# linus_v1_R2.net
KiCad netlist of a schematic drawn in EAGLE
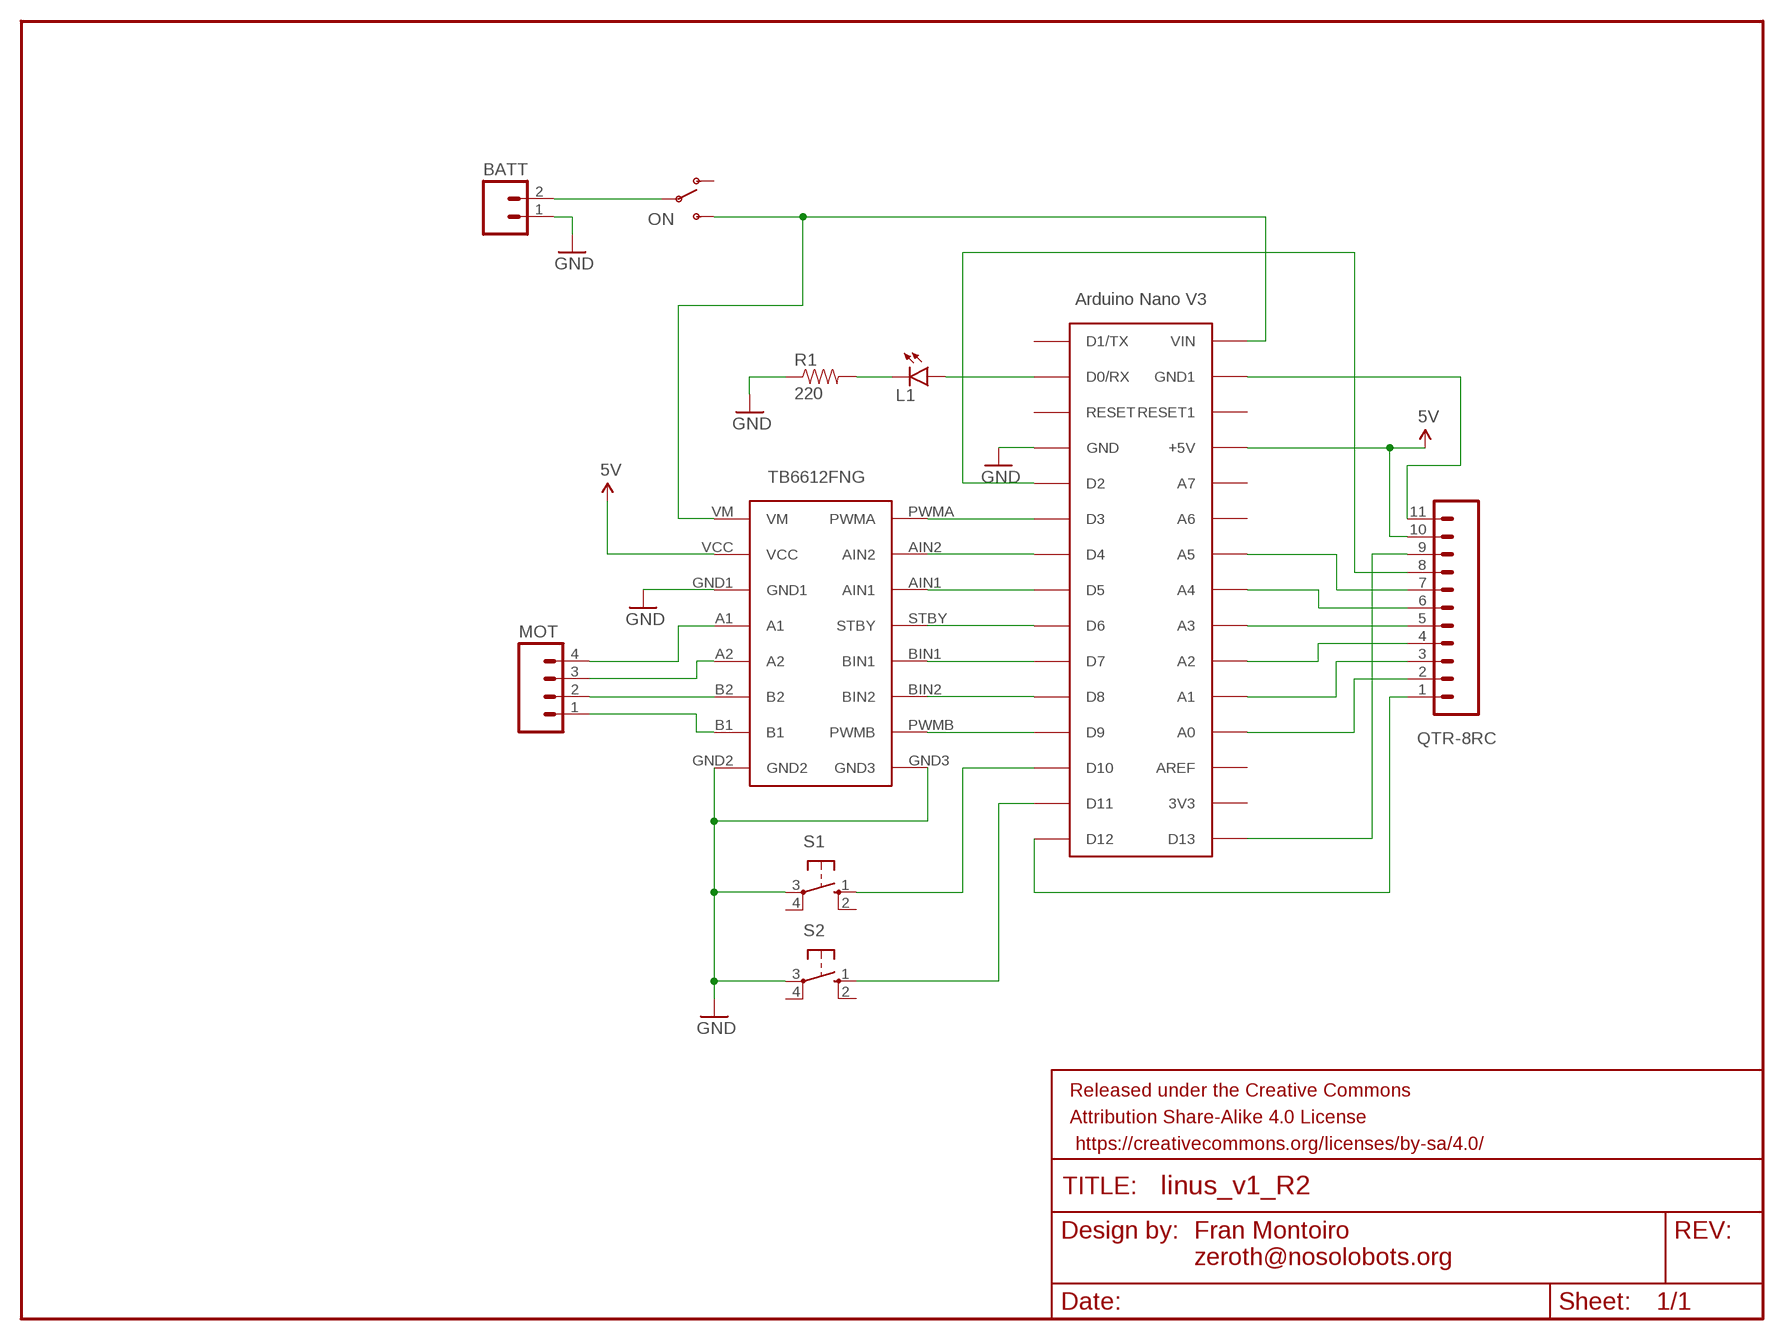
[diagram p0: schematic, sheet 1]

(export (version "E")
  (design (tool "Eeschema 10.0.6"))
  (components
    (comp (ref "BATT")
      (value "M02PTH")
      (footprint "eagle-import:1X02")
      (libsource (lib "eagle-import") (part "M02PTH"))
    )
    (comp (ref "FRAME1")
      (value "FRAME-LETTERNO_PACKAGE")
      (footprint "eagle-import:DUMMY")
      (fields (field (name "DESIGNER") "Nobody"))
      (libsource (lib "eagle-import") (part "FRAME-LETTERNO_PACKAGE"))
    )
    (comp (ref "L1")
      (value "LED5MM")
      (footprint "eagle-import:LED5MM")
      (libsource (lib "eagle-import") (part "LED5MM"))
    )
    (comp (ref "MOT")
      (value "M04PTH")
      (footprint "eagle-import:1X04")
      (libsource (lib "eagle-import") (part "M04PTH"))
    )
    (comp (ref "ON")
      (value "SWITCH-SPDTPTH")
      (footprint "eagle-import:SWITCH-SPDT")
      (libsource (lib "eagle-import") (part "SWITCH-SPDTPTH"))
    )
    (comp (ref "QTR-8RC")
      (value "M11PTH")
      (footprint "eagle-import:1X11")
      (libsource (lib "eagle-import") (part "M11PTH"))
    )
    (comp (ref "R1")
      (value "220")
      (footprint "eagle-import:AXIAL-0.4")
      (libsource (lib "eagle-import") (part "RESISTORPTH-1/4W"))
    )
    (comp (ref "S1")
      (value "10-XX")
      (footprint "eagle-import:B3F-10XX")
      (fields (field (name "MPN") "B3F-1000"))
      (libsource (lib "eagle-import") (part "10-XX"))
    )
    (comp (ref "S2")
      (value "10-XX")
      (footprint "eagle-import:B3F-10XX")
      (fields (field (name "MPN") "B3F-1000"))
      (libsource (lib "eagle-import") (part "10-XX"))
    )
    (comp (ref "TB1")
      (value "TB6612FNG")
      (footprint "eagle-import:TB6612FNG")
      (libsource (lib "eagle-import") (part "TB6612FNG"))
    )
    (comp (ref "U$1")
      (value "ARDUINONANO")
      (footprint "eagle-import:PDIP-32")
      (libsource (lib "eagle-import") (part "ARDUINONANO"))
    )
  )
  (nets
    (net (code "1") (name "5V") (class "Default")
      (node (ref "QTR-8RC") (pin "10") (pinfunction "10_10") (pintype "passive"))
      (node (ref "TB1") (pin "VCC") (pinfunction "VCC_VCC") (pintype "bidirectional"))
      (node (ref "U$1") (pin "+5V") (pinfunction "+5V_+5V") (pintype "bidirectional"))
    )
    (net (code "2") (name "GND") (class "Default")
      (node (ref "BATT") (pin "1") (pinfunction "1_1") (pintype "passive"))
      (node (ref "R1") (pin "P$1") (pinfunction "1_P$1") (pintype "passive"))
      (node (ref "S1") (pin "3") (pinfunction "P_3") (pintype "passive"))
      (node (ref "S2") (pin "3") (pinfunction "P_3") (pintype "passive"))
      (node (ref "TB1") (pin "GND1") (pinfunction "GND1_GND1") (pintype "bidirectional"))
      (node (ref "TB1") (pin "GND2") (pinfunction "GND2_GND2") (pintype "bidirectional"))
      (node (ref "TB1") (pin "GND3") (pinfunction "GND3_GND3") (pintype "bidirectional"))
      (node (ref "U$1") (pin "GND") (pinfunction "GND_GND") (pintype "bidirectional"))
    )
    (net (code "3") (name "Net-(L1-C)") (class "Default")
      (node (ref "L1") (pin "K") (pinfunction "C_K") (pintype "passive"))
      (node (ref "R1") (pin "P$2") (pinfunction "2_P$2") (pintype "passive"))
    )
    (net (code "4") (name "Net-(L1-PadA)") (class "Default")
      (node (ref "L1") (pin "A") (pinfunction "A_A") (pintype "passive"))
      (node (ref "U$1") (pin "D0/RX") (pinfunction "D0/RX_D0/RX") (pintype "bidirectional"))
    )
    (net (code "5") (name "Net-(MOT-Pad1)") (class "Default")
      (node (ref "MOT") (pin "1") (pinfunction "1_1") (pintype "passive"))
      (node (ref "TB1") (pin "B1") (pinfunction "B1_B1") (pintype "bidirectional"))
    )
    (net (code "6") (name "Net-(MOT-Pad2)") (class "Default")
      (node (ref "MOT") (pin "2") (pinfunction "2_2") (pintype "passive"))
      (node (ref "TB1") (pin "B2") (pinfunction "B2_B2") (pintype "bidirectional"))
    )
    (net (code "7") (name "Net-(MOT-Pad3)") (class "Default")
      (node (ref "MOT") (pin "3") (pinfunction "3_3") (pintype "passive"))
      (node (ref "TB1") (pin "A2") (pinfunction "A2_A2") (pintype "bidirectional"))
    )
    (net (code "8") (name "Net-(MOT-Pad4)") (class "Default")
      (node (ref "MOT") (pin "4") (pinfunction "4_4") (pintype "passive"))
      (node (ref "TB1") (pin "A1") (pinfunction "A1_A1") (pintype "bidirectional"))
    )
    (net (code "9") (name "Net-(ON-P)") (class "Default")
      (node (ref "BATT") (pin "2") (pinfunction "2_2") (pintype "passive"))
      (node (ref "ON") (pin "2") (pinfunction "P_2") (pintype "passive"))
    )
    (net (code "10") (name "Net-(ON-S)") (class "Default")
      (node (ref "ON") (pin "3") (pinfunction "S_3") (pintype "passive"))
      (node (ref "TB1") (pin "VM") (pinfunction "VM_VM") (pintype "bidirectional"))
      (node (ref "U$1") (pin "VIN") (pinfunction "VIN_VIN") (pintype "bidirectional"))
    )
    (net (code "11") (name "Net-(QTR-8RC-Pad1)") (class "Default")
      (node (ref "QTR-8RC") (pin "1") (pinfunction "1_1") (pintype "passive"))
      (node (ref "U$1") (pin "D12") (pinfunction "D12_D12") (pintype "bidirectional"))
    )
    (net (code "12") (name "Net-(QTR-8RC-Pad8)") (class "Default")
      (node (ref "QTR-8RC") (pin "8") (pinfunction "8_8") (pintype "passive"))
      (node (ref "U$1") (pin "D2") (pinfunction "D2_D2") (pintype "bidirectional"))
    )
    (net (code "13") (name "Net-(QTR-8RC-Pad9)") (class "Default")
      (node (ref "QTR-8RC") (pin "9") (pinfunction "9_9") (pintype "passive"))
      (node (ref "U$1") (pin "D13") (pinfunction "D13_D13") (pintype "bidirectional"))
    )
    (net (code "14") (name "Net-(QTR-8RC-Pad11)") (class "Default")
      (node (ref "QTR-8RC") (pin "11") (pinfunction "11_11") (pintype "passive"))
      (node (ref "U$1") (pin "GND1") (pinfunction "GND1_GND1") (pintype "bidirectional"))
    )
    (net (code "15") (name "Net-(S1-S)") (class "Default")
      (node (ref "S1") (pin "1") (pinfunction "S_1") (pintype "passive"))
      (node (ref "U$1") (pin "D10") (pinfunction "D10_D10") (pintype "bidirectional"))
    )
    (net (code "16") (name "Net-(S2-S)") (class "Default")
      (node (ref "S2") (pin "1") (pinfunction "S_1") (pintype "passive"))
      (node (ref "U$1") (pin "D11") (pinfunction "D11_D11") (pintype "bidirectional"))
    )
    (net (code "17") (name "Net-(TB1-PadAIN1)") (class "Default")
      (node (ref "TB1") (pin "AIN1") (pinfunction "AIN1_AIN1") (pintype "bidirectional"))
      (node (ref "U$1") (pin "D5") (pinfunction "D5_D5") (pintype "bidirectional"))
    )
    (net (code "18") (name "Net-(TB1-PadAIN2)") (class "Default")
      (node (ref "TB1") (pin "AIN2") (pinfunction "AIN2_AIN2") (pintype "bidirectional"))
      (node (ref "U$1") (pin "D4") (pinfunction "D4_D4") (pintype "bidirectional"))
    )
    (net (code "19") (name "Net-(TB1-PadBIN1)") (class "Default")
      (node (ref "TB1") (pin "BIN1") (pinfunction "BIN1_BIN1") (pintype "bidirectional"))
      (node (ref "U$1") (pin "D7") (pinfunction "D7_D7") (pintype "bidirectional"))
    )
    (net (code "20") (name "Net-(TB1-PadBIN2)") (class "Default")
      (node (ref "TB1") (pin "BIN2") (pinfunction "BIN2_BIN2") (pintype "bidirectional"))
      (node (ref "U$1") (pin "D8") (pinfunction "D8_D8") (pintype "bidirectional"))
    )
    (net (code "21") (name "Net-(TB1-PadPWMA)") (class "Default")
      (node (ref "TB1") (pin "PWMA") (pinfunction "PWMA_PWMA") (pintype "bidirectional"))
      (node (ref "U$1") (pin "D3") (pinfunction "D3_D3") (pintype "bidirectional"))
    )
    (net (code "22") (name "Net-(TB1-PadPWMB)") (class "Default")
      (node (ref "TB1") (pin "PWMB") (pinfunction "PWMB_PWMB") (pintype "bidirectional"))
      (node (ref "U$1") (pin "D9") (pinfunction "D9_D9") (pintype "bidirectional"))
    )
    (net (code "23") (name "Net-(TB1-PadSTBY)") (class "Default")
      (node (ref "TB1") (pin "STBY") (pinfunction "STBY_STBY") (pintype "bidirectional"))
      (node (ref "U$1") (pin "D6") (pinfunction "D6_D6") (pintype "bidirectional"))
    )
    (net (code "24") (name "Net-(U$1-A0)") (class "Default")
      (node (ref "QTR-8RC") (pin "2") (pinfunction "2_2") (pintype "passive"))
      (node (ref "U$1") (pin "A7") (pinfunction "A0_A7") (pintype "bidirectional"))
    )
    (net (code "25") (name "Net-(U$1-A1)") (class "Default")
      (node (ref "QTR-8RC") (pin "3") (pinfunction "3_3") (pintype "passive"))
      (node (ref "U$1") (pin "A6") (pinfunction "A1_A6") (pintype "bidirectional"))
    )
    (net (code "26") (name "Net-(U$1-A2)") (class "Default")
      (node (ref "QTR-8RC") (pin "4") (pinfunction "4_4") (pintype "passive"))
      (node (ref "U$1") (pin "A5") (pinfunction "A2_A5") (pintype "bidirectional"))
    )
    (net (code "27") (name "Net-(U$1-A3)") (class "Default")
      (node (ref "QTR-8RC") (pin "5") (pinfunction "5_5") (pintype "passive"))
      (node (ref "U$1") (pin "A4") (pinfunction "A3_A4") (pintype "bidirectional"))
    )
    (net (code "28") (name "Net-(U$1-A4)") (class "Default")
      (node (ref "QTR-8RC") (pin "6") (pinfunction "6_6") (pintype "passive"))
      (node (ref "U$1") (pin "A3") (pinfunction "A4_A3") (pintype "bidirectional"))
    )
    (net (code "29") (name "Net-(U$1-A5)") (class "Default")
      (node (ref "QTR-8RC") (pin "7") (pinfunction "7_7") (pintype "passive"))
      (node (ref "U$1") (pin "A2") (pinfunction "A5_A2") (pintype "bidirectional"))
    )
    (net (code "30") (name "unconnected-(ON-O-Pad1)") (class "Default")
      (node (ref "ON") (pin "1") (pinfunction "O_1") (pintype "passive"))
    )
    (net (code "31") (name "unconnected-(S1-P1-Pad4)") (class "Default")
      (node (ref "S1") (pin "4") (pinfunction "P1_4") (pintype "passive"))
    )
    (net (code "32") (name "unconnected-(S1-S1-Pad2)") (class "Default")
      (node (ref "S1") (pin "2") (pinfunction "S1_2") (pintype "passive"))
    )
    (net (code "33") (name "unconnected-(S2-P1-Pad4)") (class "Default")
      (node (ref "S2") (pin "4") (pinfunction "P1_4") (pintype "passive"))
    )
    (net (code "34") (name "unconnected-(S2-S1-Pad2)") (class "Default")
      (node (ref "S2") (pin "2") (pinfunction "S1_2") (pintype "passive"))
    )
    (net (code "35") (name "unconnected-(U$1-A6-PadA1)") (class "Default")
      (node (ref "U$1") (pin "A1") (pinfunction "A6_A1") (pintype "bidirectional"))
    )
    (net (code "36") (name "unconnected-(U$1-A7-PadA0)") (class "Default")
      (node (ref "U$1") (pin "A0") (pinfunction "A7_A0") (pintype "bidirectional"))
    )
    (net (code "37") (name "unconnected-(U$1-Pad3V3)") (class "Default")
      (node (ref "U$1") (pin "3V3") (pinfunction "3V3_3V3") (pintype "bidirectional"))
    )
    (net (code "38") (name "unconnected-(U$1-PadAREF)") (class "Default")
      (node (ref "U$1") (pin "AREF") (pinfunction "AREF_AREF") (pintype "bidirectional"))
    )
    (net (code "39") (name "unconnected-(U$1-PadD1{slash}TX)") (class "Default")
      (node (ref "U$1") (pin "D1/TX") (pinfunction "D1/TX_D1/TX") (pintype "bidirectional"))
    )
    (net (code "40") (name "unconnected-(U$1-PadRESET)") (class "Default")
      (node (ref "U$1") (pin "RESET") (pinfunction "RESET_RESET") (pintype "bidirectional"))
    )
    (net (code "41") (name "unconnected-(U$1-PadRESET1)") (class "Default")
      (node (ref "U$1") (pin "RESET1") (pinfunction "RESET1_RESET1") (pintype "bidirectional"))
    )
  )
)
